# gs.net
KiCad netlist of a schematic drawn in EAGLE
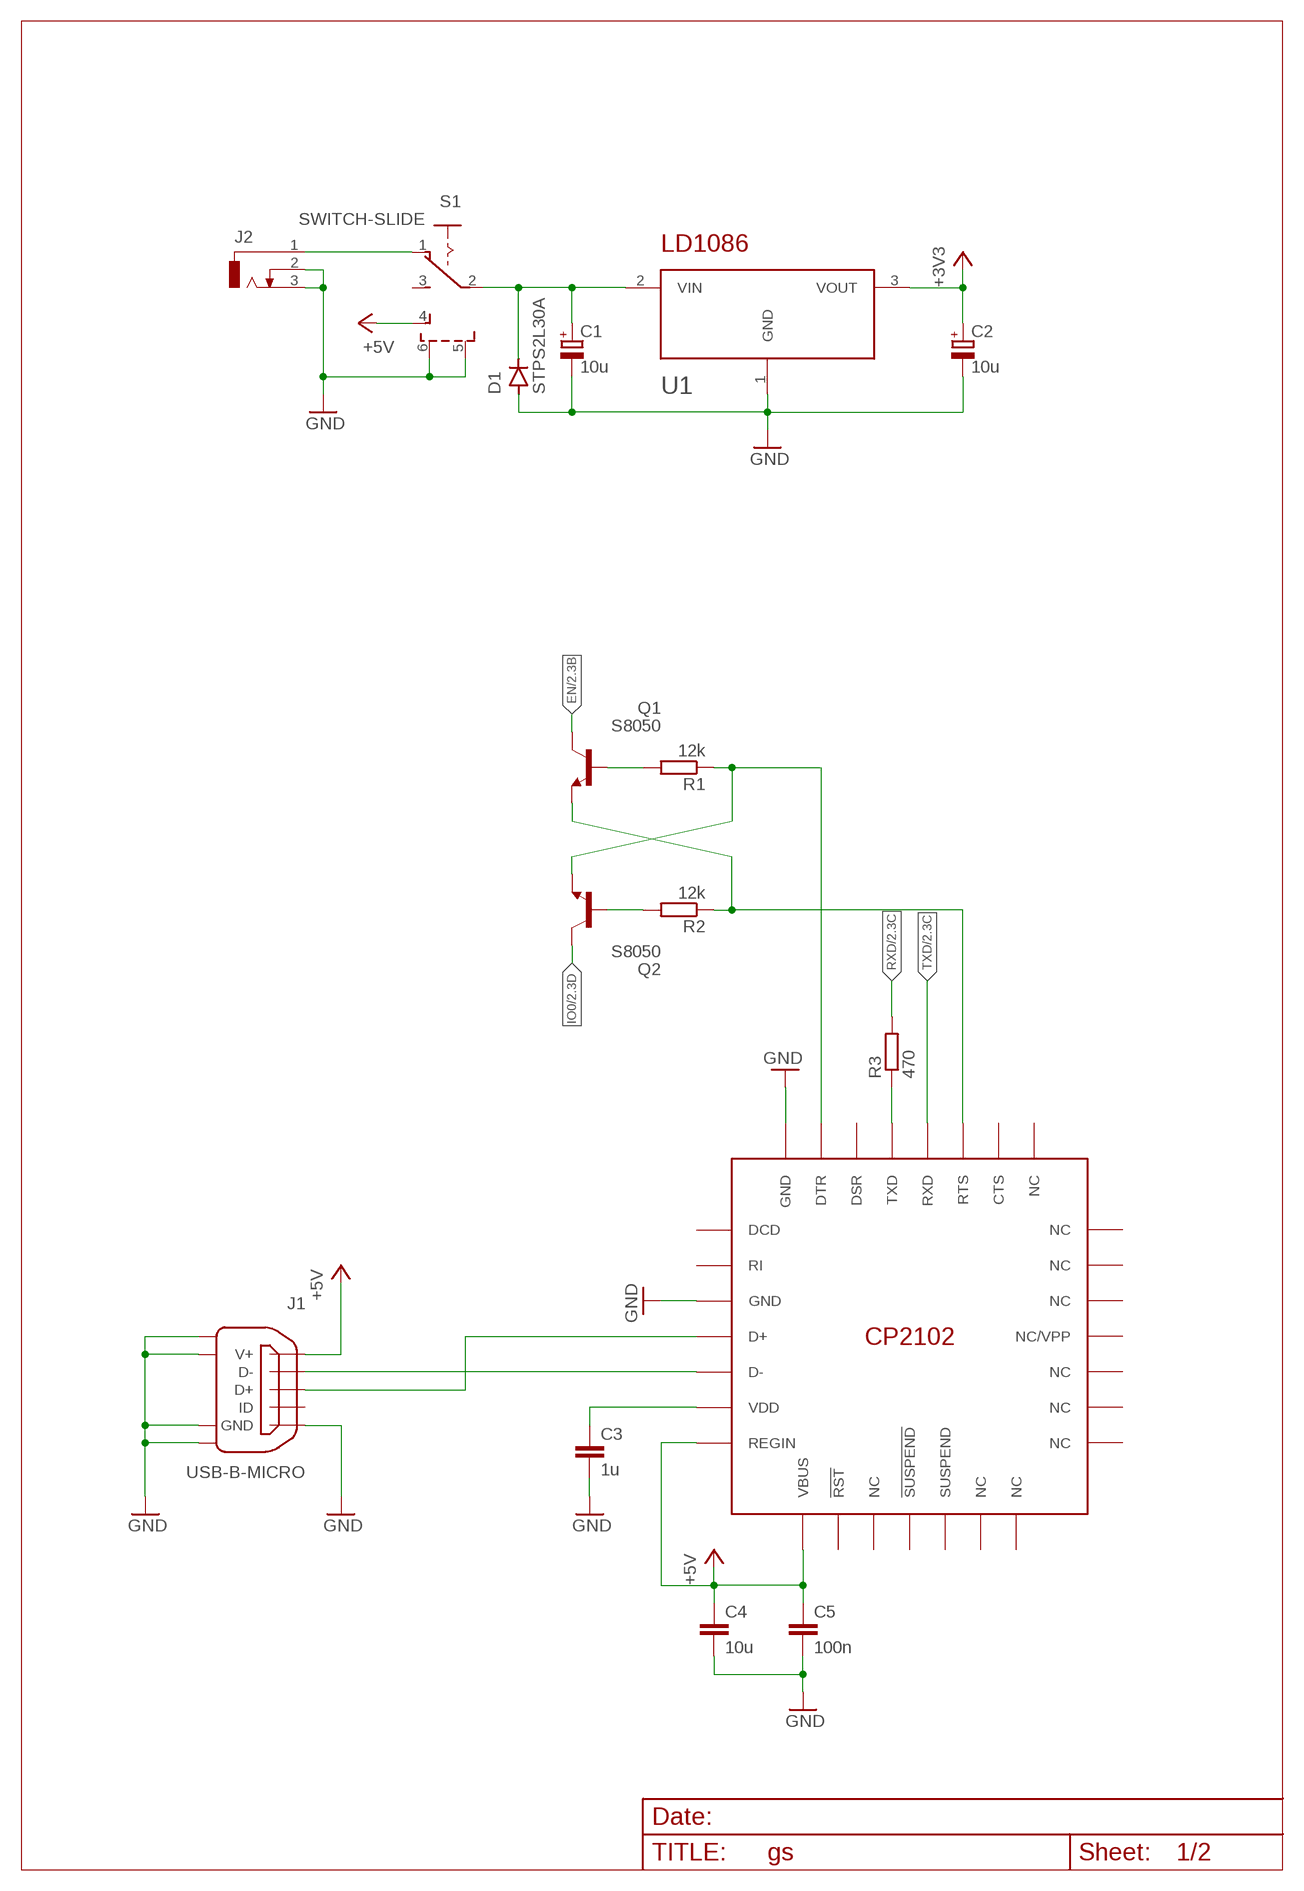
[diagram p0: schematic, sheet 1]
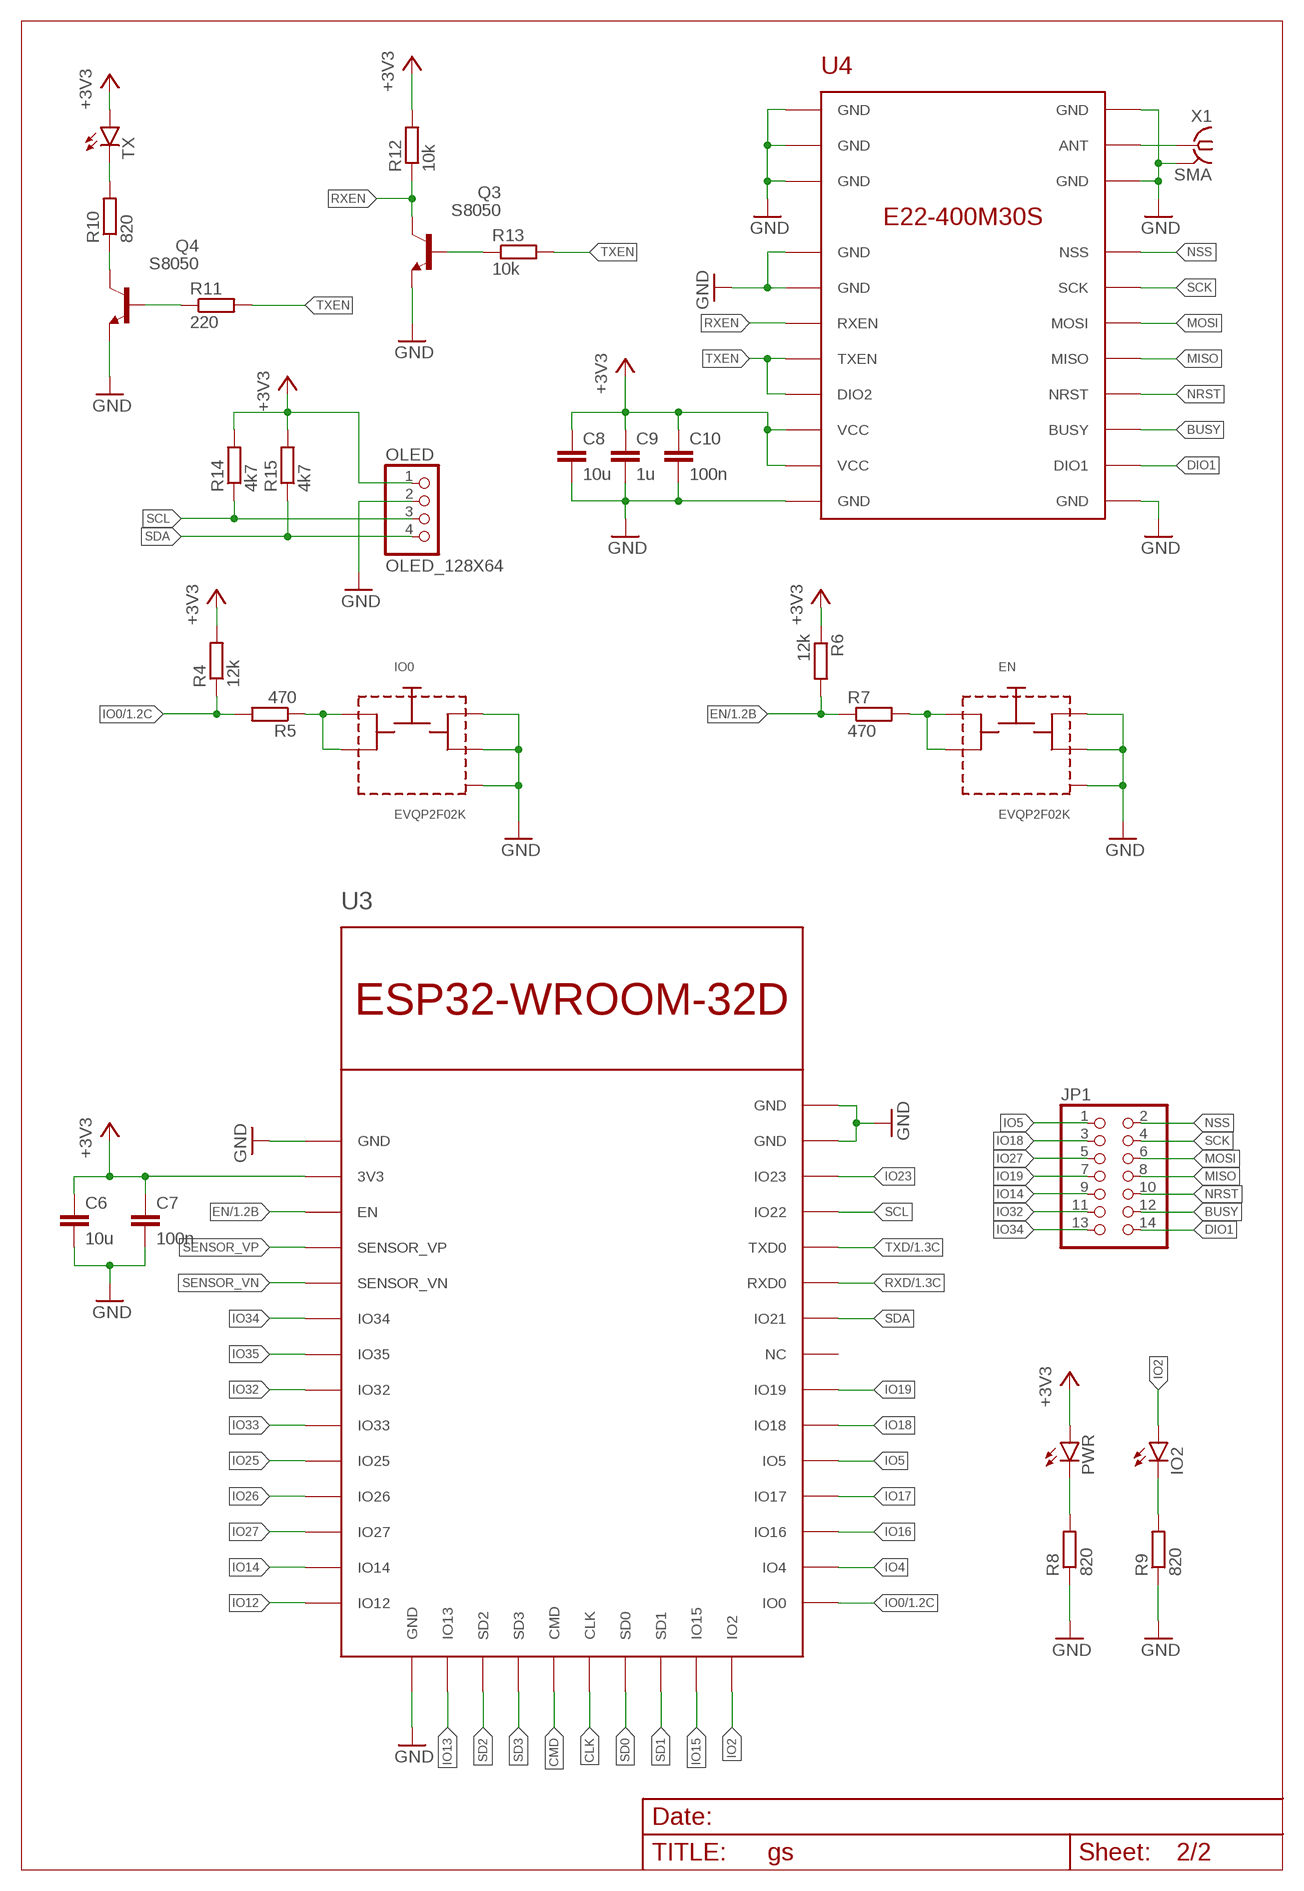
[diagram p1: schematic, sheet 2]

(export (version "E")
  (design (tool "Eeschema 10.0.6"))
  (components
    (comp (ref "C6")
      (value "10u")
      (footprint "eagle-import:C0805")
      (libsource (lib "eagle-import") (part "C-EUC0805"))
    )
    (comp (ref "C7")
      (value "100n")
      (footprint "eagle-import:C0805")
      (libsource (lib "eagle-import") (part "C-EUC0805"))
    )
    (comp (ref "C8")
      (value "10u")
      (footprint "eagle-import:C0805")
      (libsource (lib "eagle-import") (part "C-EUC0805"))
    )
    (comp (ref "C9")
      (value "1u")
      (footprint "eagle-import:C0805")
      (libsource (lib "eagle-import") (part "C-EUC0805"))
    )
    (comp (ref "C10")
      (value "100n")
      (footprint "eagle-import:C0805")
      (libsource (lib "eagle-import") (part "C-EUC0805"))
    )
    (comp (ref "EN")
      (value "EVQP2F02K")
      (footprint "eagle-import:EVQP2F02K")
      (libsource (lib "eagle-import") (part "EVQP2F02K"))
    )
    (comp (ref "IO0")
      (value "EVQP2F02K")
      (footprint "eagle-import:EVQP2F02K")
      (libsource (lib "eagle-import") (part "EVQP2F02K"))
    )
    (comp (ref "IO2")
      (value "LEDCHIP-LED0805")
      (footprint "eagle-import:CHIP-LED0805")
      (libsource (lib "eagle-import") (part "LEDCHIP-LED0805"))
    )
    (comp (ref "JP1")
      (value "PINHD-2X7")
      (footprint "eagle-import:2X07")
      (libsource (lib "eagle-import") (part "PINHD-2X7"))
    )
    (comp (ref "OLED")
      (value "OLED_128X64")
      (footprint "eagle-import:OLED_128X64")
      (libsource (lib "eagle-import") (part "OLED_128X64"))
    )
    (comp (ref "PWR")
      (value "LEDCHIP-LED0805")
      (footprint "eagle-import:CHIP-LED0805")
      (libsource (lib "eagle-import") (part "LEDCHIP-LED0805"))
    )
    (comp (ref "Q3")
      (value "S8050")
      (footprint "eagle-import:SOT95P237X110-3N")
      (libsource (lib "eagle-import") (part "S8050"))
    )
    (comp (ref "Q4")
      (value "S8050")
      (footprint "eagle-import:SOT95P237X110-3N")
      (libsource (lib "eagle-import") (part "S8050"))
    )
    (comp (ref "R4")
      (value "12k")
      (footprint "eagle-import:R0805")
      (libsource (lib "eagle-import") (part "R-EU_R0805"))
    )
    (comp (ref "R5")
      (value "470")
      (footprint "eagle-import:R0805")
      (libsource (lib "eagle-import") (part "R-EU_R0805"))
    )
    (comp (ref "R6")
      (value "12k")
      (footprint "eagle-import:R0805")
      (libsource (lib "eagle-import") (part "R-EU_R0805"))
    )
    (comp (ref "R7")
      (value "470")
      (footprint "eagle-import:R0805")
      (libsource (lib "eagle-import") (part "R-EU_R0805"))
    )
    (comp (ref "R8")
      (value "820")
      (footprint "eagle-import:R0805")
      (libsource (lib "eagle-import") (part "R-EU_R0805"))
    )
    (comp (ref "R9")
      (value "820")
      (footprint "eagle-import:R0805")
      (libsource (lib "eagle-import") (part "R-EU_R0805"))
    )
    (comp (ref "R10")
      (value "820")
      (footprint "eagle-import:R0805")
      (libsource (lib "eagle-import") (part "R-EU_R0805"))
    )
    (comp (ref "R11")
      (value "220")
      (footprint "eagle-import:R0805")
      (libsource (lib "eagle-import") (part "R-EU_R0805"))
    )
    (comp (ref "R12")
      (value "10k")
      (footprint "eagle-import:R0805")
      (libsource (lib "eagle-import") (part "R-EU_R0805"))
    )
    (comp (ref "R13")
      (value "10k")
      (footprint "eagle-import:R0805")
      (libsource (lib "eagle-import") (part "R-EU_R0805"))
    )
    (comp (ref "R14")
      (value "4k7")
      (footprint "eagle-import:R0805")
      (libsource (lib "eagle-import") (part "R-EU_R0805"))
    )
    (comp (ref "R15")
      (value "4k7")
      (footprint "eagle-import:R0805")
      (libsource (lib "eagle-import") (part "R-EU_R0805"))
    )
    (comp (ref "TX")
      (value "LEDCHIP-LED0805")
      (footprint "eagle-import:CHIP-LED0805")
      (libsource (lib "eagle-import") (part "LEDCHIP-LED0805"))
    )
    (comp (ref "U3")
      (value "ESP32-WROOM-32D")
      (footprint "eagle-import:ESP32-SOLO-1")
      (libsource (lib "eagle-import") (part "ESP32-WROOM-32D"))
    )
    (comp (ref "U4")
      (value "E22-400M30S")
      (footprint "eagle-import:E22-400M30S")
      (libsource (lib "eagle-import") (part "E22-400M30S"))
    )
    (comp (ref "X1")
      (value "SMA")
      (footprint "eagle-import:SMA")
      (fields (field (name "TME") "RF2145AT1750GHDW"))
      (libsource (lib "eagle-import") (part "SMA"))
    )
    (comp (ref "C1")
      (value "10u")
      (footprint "eagle-import:SMC_C")
      (libsource (lib "eagle-import") (part "CPOL-EUSMCC"))
    )
    (comp (ref "C2")
      (value "10u")
      (footprint "eagle-import:SMC_C")
      (libsource (lib "eagle-import") (part "CPOL-EUSMCC"))
    )
    (comp (ref "C3")
      (value "1u")
      (footprint "eagle-import:C0805")
      (libsource (lib "eagle-import") (part "C-EUC0805"))
    )
    (comp (ref "C4")
      (value "10u")
      (footprint "eagle-import:C0805")
      (libsource (lib "eagle-import") (part "C-EUC0805"))
    )
    (comp (ref "C5")
      (value "100n")
      (footprint "eagle-import:C0805")
      (libsource (lib "eagle-import") (part "C-EUC0805"))
    )
    (comp (ref "D1")
      (value "STPS2L30A")
      (footprint "eagle-import:DIOM4225X245N")
      (libsource (lib "eagle-import") (part "STPS2L30A"))
    )
    (comp (ref "J1")
      (value "USB-B-MICRO")
      (footprint "eagle-import:USB-B-MICRO")
      (libsource (lib "eagle-import") (part "USB-B-MICRO"))
    )
    (comp (ref "J2")
      (value "DCJ0303")
      (footprint "eagle-import:DCJ0303")
      (fields (field (name "TME") "1613-21"))
      (libsource (lib "eagle-import") (part "DCJ0303"))
    )
    (comp (ref "Q1")
      (value "S8050")
      (footprint "eagle-import:SOT95P237X110-3N")
      (libsource (lib "eagle-import") (part "S8050"))
    )
    (comp (ref "Q2")
      (value "S8050")
      (footprint "eagle-import:SOT95P237X110-3N")
      (libsource (lib "eagle-import") (part "S8050"))
    )
    (comp (ref "R1")
      (value "12k")
      (footprint "eagle-import:R0805")
      (libsource (lib "eagle-import") (part "R-EU_R0805"))
    )
    (comp (ref "R2")
      (value "12k")
      (footprint "eagle-import:R0805")
      (libsource (lib "eagle-import") (part "R-EU_R0805"))
    )
    (comp (ref "R3")
      (value "470")
      (footprint "eagle-import:R0805")
      (libsource (lib "eagle-import") (part "R-EU_R0805"))
    )
    (comp (ref "S1")
      (value "SWITCH-SLIDE")
      (footprint "eagle-import:SWITCH-SLIDE")
      (libsource (lib "eagle-import") (part "SWITCH-SLIDE"))
    )
    (comp (ref "U1")
      (value "LD1086DT33TR")
      (footprint "eagle-import:TO228P972X240-3N")
      (libsource (lib "eagle-import") (part "LD1086DT33TR"))
    )
    (comp (ref "U2")
      (value "CP2102")
      (footprint "eagle-import:QFN50P500X500X100-29T300N")
      (libsource (lib "eagle-import") (part "CP2102"))
    )
  )
  (nets
    (net (code "1") (name "+3V3") (class "Default")
      (node (ref "C10") (pin "1") (pinfunction "1_1") (pintype "passive"))
      (node (ref "C2") (pin "+") (pinfunction "+_+") (pintype "passive"))
      (node (ref "C6") (pin "1") (pinfunction "1_1") (pintype "passive"))
      (node (ref "C7") (pin "1") (pinfunction "1_1") (pintype "passive"))
      (node (ref "C8") (pin "1") (pinfunction "1_1") (pintype "passive"))
      (node (ref "C9") (pin "1") (pinfunction "1_1") (pintype "passive"))
      (node (ref "OLED") (pin "1") (pinfunction "1_1") (pintype "passive"))
      (node (ref "PWR") (pin "A") (pinfunction "A_A") (pintype "passive"))
      (node (ref "R12") (pin "2") (pinfunction "2_2") (pintype "passive"))
      (node (ref "R14") (pin "2") (pinfunction "2_2") (pintype "passive"))
      (node (ref "R15") (pin "2") (pinfunction "2_2") (pintype "passive"))
      (node (ref "R4") (pin "2") (pinfunction "2_2") (pintype "passive"))
      (node (ref "R6") (pin "1") (pinfunction "1_1") (pintype "passive"))
      (node (ref "TX") (pin "A") (pinfunction "A_A") (pintype "passive"))
      (node (ref "U1") (pin "3") (pinfunction "VOUT_3") (pintype "bidirectional"))
      (node (ref "U3") (pin "2") (pinfunction "3V3_2") (pintype "bidirectional"))
      (node (ref "U4") (pin "10") (pinfunction "VCC_10") (pintype "bidirectional"))
      (node (ref "U4") (pin "9") (pinfunction "VCC_9") (pintype "bidirectional"))
    )
    (net (code "2") (name "+5V") (class "Default")
      (node (ref "C4") (pin "1") (pinfunction "1_1") (pintype "passive"))
      (node (ref "C5") (pin "1") (pinfunction "1_1") (pintype "passive"))
      (node (ref "J1") (pin "1") (pinfunction "V+_1") (pintype "passive"))
      (node (ref "S1") (pin "4") (pinfunction "4_4") (pintype "passive"))
      (node (ref "U2") (pin "7") (pinfunction "REGIN_7") (pintype "bidirectional"))
      (node (ref "U2") (pin "8") (pinfunction "VBUS_8") (pintype "bidirectional"))
    )
    (net (code "3") (name "BUSY") (class "Default")
      (node (ref "JP1") (pin "12") (pinfunction "12_12") (pintype "passive"))
      (node (ref "U4") (pin "14") (pinfunction "BUSY_14") (pintype "bidirectional"))
    )
    (net (code "4") (name "CLK") (class "Default")
      (node (ref "U3") (pin "20") (pinfunction "CLK_20") (pintype "bidirectional"))
    )
    (net (code "5") (name "CMD") (class "Default")
      (node (ref "U3") (pin "19") (pinfunction "CMD_19") (pintype "bidirectional"))
    )
    (net (code "6") (name "DIO1") (class "Default")
      (node (ref "JP1") (pin "14") (pinfunction "14_14") (pintype "passive"))
      (node (ref "U4") (pin "13") (pinfunction "DIO1_13") (pintype "bidirectional"))
    )
    (net (code "7") (name "EN") (class "Default")
      (node (ref "Q1") (pin "3") (pinfunction "C_3") (pintype "passive"))
      (node (ref "R6") (pin "2") (pinfunction "2_2") (pintype "passive"))
      (node (ref "R7") (pin "1") (pinfunction "1_1") (pintype "passive"))
      (node (ref "U3") (pin "3") (pinfunction "EN_3") (pintype "bidirectional"))
    )
    (net (code "8") (name "GND") (class "Default")
      (node (ref "C1") (pin "-") (pinfunction "-_-") (pintype "passive"))
      (node (ref "C10") (pin "2") (pinfunction "2_2") (pintype "passive"))
      (node (ref "C2") (pin "-") (pinfunction "-_-") (pintype "passive"))
      (node (ref "C3") (pin "2") (pinfunction "2_2") (pintype "passive"))
      (node (ref "C4") (pin "2") (pinfunction "2_2") (pintype "passive"))
      (node (ref "C5") (pin "2") (pinfunction "2_2") (pintype "passive"))
      (node (ref "C6") (pin "2") (pinfunction "2_2") (pintype "passive"))
      (node (ref "C7") (pin "2") (pinfunction "2_2") (pintype "passive"))
      (node (ref "C8") (pin "2") (pinfunction "2_2") (pintype "passive"))
      (node (ref "C9") (pin "2") (pinfunction "2_2") (pintype "passive"))
      (node (ref "D1") (pin "2") (pinfunction "A_2") (pintype "passive"))
      (node (ref "EN") (pin "3") (pinfunction "P$3_3") (pintype "passive"))
      (node (ref "EN") (pin "4") (pinfunction "P$4_4") (pintype "passive"))
      (node (ref "EN") (pin "5") (pinfunction "P$5_5") (pintype "passive"))
      (node (ref "IO0") (pin "3") (pinfunction "P$3_3") (pintype "passive"))
      (node (ref "IO0") (pin "4") (pinfunction "P$4_4") (pintype "passive"))
      (node (ref "IO0") (pin "5") (pinfunction "P$5_5") (pintype "passive"))
      (node (ref "J1") (pin "5") (pinfunction "GND_5") (pintype "passive"))
      (node (ref "J1") (pin "6") (pinfunction "6_6") (pintype "passive"))
      (node (ref "J1") (pin "7") (pinfunction "7_7") (pintype "passive"))
      (node (ref "J1") (pin "8") (pinfunction "8_8") (pintype "passive"))
      (node (ref "J1") (pin "9") (pinfunction "9_9") (pintype "passive"))
      (node (ref "J2") (pin "2") (pinfunction "2_2") (pintype "passive"))
      (node (ref "J2") (pin "3") (pinfunction "3_3") (pintype "passive"))
      (node (ref "OLED") (pin "2") (pinfunction "2_2") (pintype "passive"))
      (node (ref "Q3") (pin "2") (pinfunction "E_2") (pintype "passive"))
      (node (ref "Q4") (pin "2") (pinfunction "E_2") (pintype "passive"))
      (node (ref "R8") (pin "1") (pinfunction "1_1") (pintype "passive"))
      (node (ref "R9") (pin "1") (pinfunction "1_1") (pintype "passive"))
      (node (ref "S1") (pin "5") (pinfunction "S1_5") (pintype "passive"))
      (node (ref "S1") (pin "6") (pinfunction "S2_6") (pintype "passive"))
      (node (ref "U1") (pin "1") (pinfunction "GND_1") (pintype "bidirectional"))
      (node (ref "U2") (pin "29") (pinfunction "GND_29") (pintype "bidirectional"))
      (node (ref "U2") (pin "3") (pinfunction "GND_3") (pintype "bidirectional"))
      (node (ref "U3") (pin "1") (pinfunction "GND_1") (pintype "bidirectional"))
      (node (ref "U3") (pin "15") (pinfunction "GND_15") (pintype "bidirectional"))
      (node (ref "U3") (pin "38") (pinfunction "GND_38") (pintype "bidirectional"))
      (node (ref "U3") (pin "39") (pinfunction "GND_39") (pintype "bidirectional"))
      (node (ref "U4") (pin "1") (pinfunction "GND_1") (pintype "bidirectional"))
      (node (ref "U4") (pin "11") (pinfunction "GND_11") (pintype "bidirectional"))
      (node (ref "U4") (pin "12") (pinfunction "GND_12") (pintype "bidirectional"))
      (node (ref "U4") (pin "2") (pinfunction "GND_2") (pintype "bidirectional"))
      (node (ref "U4") (pin "20") (pinfunction "GND_20") (pintype "bidirectional"))
      (node (ref "U4") (pin "22") (pinfunction "GND_22") (pintype "bidirectional"))
      (node (ref "U4") (pin "3") (pinfunction "GND_3") (pintype "bidirectional"))
      (node (ref "U4") (pin "4") (pinfunction "GND_4") (pintype "bidirectional"))
      (node (ref "U4") (pin "5") (pinfunction "GND_5") (pintype "bidirectional"))
      (node (ref "X1") (pin "G@1") (pinfunction "2_G@1") (pintype "passive"))
      (node (ref "X1") (pin "G@2") (pinfunction "2_G@2") (pintype "passive"))
      (node (ref "X1") (pin "G@3") (pinfunction "2_G@3") (pintype "passive"))
      (node (ref "X1") (pin "G@4") (pinfunction "2_G@4") (pintype "passive"))
    )
    (net (code "9") (name "IO0") (class "Default")
      (node (ref "Q2") (pin "3") (pinfunction "C_3") (pintype "passive"))
      (node (ref "R4") (pin "1") (pinfunction "1_1") (pintype "passive"))
      (node (ref "R5") (pin "2") (pinfunction "2_2") (pintype "passive"))
      (node (ref "U3") (pin "25") (pinfunction "IO0_25") (pintype "bidirectional"))
    )
    (net (code "10") (name "IO2") (class "Default")
      (node (ref "IO2") (pin "A") (pinfunction "A_A") (pintype "passive"))
      (node (ref "U3") (pin "24") (pinfunction "IO2_24") (pintype "bidirectional"))
    )
    (net (code "11") (name "IO4") (class "Default")
      (node (ref "U3") (pin "26") (pinfunction "IO4_26") (pintype "bidirectional"))
    )
    (net (code "12") (name "IO5") (class "Default")
      (node (ref "JP1") (pin "1") (pinfunction "1_1") (pintype "passive"))
      (node (ref "U3") (pin "29") (pinfunction "IO5_29") (pintype "bidirectional"))
    )
    (net (code "13") (name "IO12") (class "Default")
      (node (ref "U3") (pin "14") (pinfunction "IO12_14") (pintype "bidirectional"))
    )
    (net (code "14") (name "IO13") (class "Default")
      (node (ref "U3") (pin "16") (pinfunction "IO13_16") (pintype "bidirectional"))
    )
    (net (code "15") (name "IO14") (class "Default")
      (node (ref "JP1") (pin "9") (pinfunction "9_9") (pintype "passive"))
      (node (ref "U3") (pin "13") (pinfunction "IO14_13") (pintype "bidirectional"))
    )
    (net (code "16") (name "IO15") (class "Default")
      (node (ref "U3") (pin "23") (pinfunction "IO15_23") (pintype "bidirectional"))
    )
    (net (code "17") (name "IO16") (class "Default")
      (node (ref "U3") (pin "27") (pinfunction "IO16_27") (pintype "bidirectional"))
    )
    (net (code "18") (name "IO17") (class "Default")
      (node (ref "U3") (pin "28") (pinfunction "IO17_28") (pintype "bidirectional"))
    )
    (net (code "19") (name "IO18") (class "Default")
      (node (ref "JP1") (pin "3") (pinfunction "3_3") (pintype "passive"))
      (node (ref "U3") (pin "30") (pinfunction "IO18_30") (pintype "bidirectional"))
    )
    (net (code "20") (name "IO19") (class "Default")
      (node (ref "JP1") (pin "7") (pinfunction "7_7") (pintype "passive"))
      (node (ref "U3") (pin "31") (pinfunction "IO19_31") (pintype "bidirectional"))
    )
    (net (code "21") (name "IO23") (class "Default")
      (node (ref "U3") (pin "37") (pinfunction "IO23_37") (pintype "bidirectional"))
    )
    (net (code "22") (name "IO25") (class "Default")
      (node (ref "U3") (pin "10") (pinfunction "IO25_10") (pintype "bidirectional"))
    )
    (net (code "23") (name "IO26") (class "Default")
      (node (ref "U3") (pin "11") (pinfunction "IO26_11") (pintype "bidirectional"))
    )
    (net (code "24") (name "IO27") (class "Default")
      (node (ref "JP1") (pin "5") (pinfunction "5_5") (pintype "passive"))
      (node (ref "U3") (pin "12") (pinfunction "IO27_12") (pintype "bidirectional"))
    )
    (net (code "25") (name "IO32") (class "Default")
      (node (ref "JP1") (pin "11") (pinfunction "11_11") (pintype "passive"))
      (node (ref "U3") (pin "8") (pinfunction "IO32_8") (pintype "bidirectional"))
    )
    (net (code "26") (name "IO33") (class "Default")
      (node (ref "U3") (pin "9") (pinfunction "IO33_9") (pintype "bidirectional"))
    )
    (net (code "27") (name "IO34") (class "Default")
      (node (ref "JP1") (pin "13") (pinfunction "13_13") (pintype "passive"))
      (node (ref "U3") (pin "6") (pinfunction "IO34_6") (pintype "bidirectional"))
    )
    (net (code "28") (name "IO35") (class "Default")
      (node (ref "U3") (pin "7") (pinfunction "IO35_7") (pintype "bidirectional"))
    )
    (net (code "29") (name "MISO") (class "Default")
      (node (ref "JP1") (pin "8") (pinfunction "8_8") (pintype "passive"))
      (node (ref "U4") (pin "16") (pinfunction "MISO_16") (pintype "bidirectional"))
    )
    (net (code "30") (name "MOSI") (class "Default")
      (node (ref "JP1") (pin "6") (pinfunction "6_6") (pintype "passive"))
      (node (ref "U4") (pin "17") (pinfunction "MOSI_17") (pintype "bidirectional"))
    )
    (net (code "31") (name "NRST") (class "Default")
      (node (ref "JP1") (pin "10") (pinfunction "10_10") (pintype "passive"))
      (node (ref "U4") (pin "15") (pinfunction "NRST_15") (pintype "bidirectional"))
    )
    (net (code "32") (name "NSS") (class "Default")
      (node (ref "JP1") (pin "2") (pinfunction "2_2") (pintype "passive"))
      (node (ref "U4") (pin "19") (pinfunction "NSS_19") (pintype "bidirectional"))
    )
    (net (code "33") (name "Net-(D1-C)") (class "Default")
      (node (ref "C1") (pin "+") (pinfunction "+_+") (pintype "passive"))
      (node (ref "D1") (pin "1") (pinfunction "C_1") (pintype "passive"))
      (node (ref "S1") (pin "2") (pinfunction "2_2") (pintype "passive"))
      (node (ref "U1") (pin "2") (pinfunction "VIN_2") (pintype "bidirectional"))
    )
    (net (code "34") (name "Net-(EN-P$1)") (class "Default")
      (node (ref "EN") (pin "1") (pinfunction "P$1_1") (pintype "passive"))
      (node (ref "EN") (pin "2") (pinfunction "P$2_2") (pintype "passive"))
      (node (ref "R7") (pin "2") (pinfunction "2_2") (pintype "passive"))
    )
    (net (code "35") (name "Net-(IO0-P$1)") (class "Default")
      (node (ref "IO0") (pin "1") (pinfunction "P$1_1") (pintype "passive"))
      (node (ref "IO0") (pin "2") (pinfunction "P$2_2") (pintype "passive"))
      (node (ref "R5") (pin "1") (pinfunction "1_1") (pintype "passive"))
    )
    (net (code "36") (name "Net-(IO2-PadC)") (class "Default")
      (node (ref "IO2") (pin "C") (pinfunction "C_C") (pintype "passive"))
      (node (ref "R9") (pin "2") (pinfunction "2_2") (pintype "passive"))
    )
    (net (code "37") (name "Net-(J1-D+)") (class "Default")
      (node (ref "J1") (pin "3") (pinfunction "D+_3") (pintype "passive"))
      (node (ref "U2") (pin "4") (pinfunction "D+_4") (pintype "bidirectional"))
    )
    (net (code "38") (name "Net-(J1-D-)") (class "Default")
      (node (ref "J1") (pin "2") (pinfunction "D-_2") (pintype "passive"))
      (node (ref "U2") (pin "5") (pinfunction "D-_5") (pintype "bidirectional"))
    )
    (net (code "39") (name "Net-(J2-Pad1)") (class "Default")
      (node (ref "J2") (pin "1") (pinfunction "1_1") (pintype "passive"))
      (node (ref "S1") (pin "1") (pinfunction "1_1") (pintype "passive"))
    )
    (net (code "40") (name "Net-(PWR-PadC)") (class "Default")
      (node (ref "PWR") (pin "C") (pinfunction "C_C") (pintype "passive"))
      (node (ref "R8") (pin "2") (pinfunction "2_2") (pintype "passive"))
    )
    (net (code "41") (name "Net-(Q1-B)") (class "Default")
      (node (ref "Q1") (pin "1") (pinfunction "B_1") (pintype "passive"))
      (node (ref "R1") (pin "2") (pinfunction "2_2") (pintype "passive"))
    )
    (net (code "42") (name "Net-(Q1-E)") (class "Default")
      (node (ref "Q1") (pin "2") (pinfunction "E_2") (pintype "passive"))
      (node (ref "R2") (pin "1") (pinfunction "1_1") (pintype "passive"))
      (node (ref "U2") (pin "24") (pinfunction "RTS_24") (pintype "bidirectional"))
    )
    (net (code "43") (name "Net-(Q2-B)") (class "Default")
      (node (ref "Q2") (pin "1") (pinfunction "B_1") (pintype "passive"))
      (node (ref "R2") (pin "2") (pinfunction "2_2") (pintype "passive"))
    )
    (net (code "44") (name "Net-(Q2-E)") (class "Default")
      (node (ref "Q2") (pin "2") (pinfunction "E_2") (pintype "passive"))
      (node (ref "R1") (pin "1") (pinfunction "1_1") (pintype "passive"))
      (node (ref "U2") (pin "28") (pinfunction "DTR_28") (pintype "bidirectional"))
    )
    (net (code "45") (name "Net-(Q3-B)") (class "Default")
      (node (ref "Q3") (pin "1") (pinfunction "B_1") (pintype "passive"))
      (node (ref "R13") (pin "1") (pinfunction "1_1") (pintype "passive"))
    )
    (net (code "46") (name "Net-(Q4-B)") (class "Default")
      (node (ref "Q4") (pin "1") (pinfunction "B_1") (pintype "passive"))
      (node (ref "R11") (pin "1") (pinfunction "1_1") (pintype "passive"))
    )
    (net (code "47") (name "Net-(Q4-C)") (class "Default")
      (node (ref "Q4") (pin "3") (pinfunction "C_3") (pintype "passive"))
      (node (ref "R10") (pin "1") (pinfunction "1_1") (pintype "passive"))
    )
    (net (code "48") (name "Net-(R10-Pad2)") (class "Default")
      (node (ref "R10") (pin "2") (pinfunction "2_2") (pintype "passive"))
      (node (ref "TX") (pin "C") (pinfunction "C_C") (pintype "passive"))
    )
    (net (code "49") (name "Net-(U2-TXD)") (class "Default")
      (node (ref "R3") (pin "1") (pinfunction "1_1") (pintype "passive"))
      (node (ref "U2") (pin "26") (pinfunction "TXD_26") (pintype "bidirectional"))
    )
    (net (code "50") (name "Net-(U2-VDD)") (class "Default")
      (node (ref "C3") (pin "1") (pinfunction "1_1") (pintype "passive"))
      (node (ref "U2") (pin "6") (pinfunction "VDD_6") (pintype "bidirectional"))
    )
    (net (code "51") (name "Net-(U4-ANT)") (class "Default")
      (node (ref "U4") (pin "21") (pinfunction "ANT_21") (pintype "bidirectional"))
      (node (ref "X1") (pin "1") (pinfunction "1_1") (pintype "passive"))
    )
    (net (code "52") (name "RXD") (class "Default")
      (node (ref "R3") (pin "2") (pinfunction "2_2") (pintype "passive"))
      (node (ref "U3") (pin "34") (pinfunction "RXD0_34") (pintype "bidirectional"))
    )
    (net (code "53") (name "RXEN") (class "Default")
      (node (ref "Q3") (pin "3") (pinfunction "C_3") (pintype "passive"))
      (node (ref "R12") (pin "1") (pinfunction "1_1") (pintype "passive"))
      (node (ref "U4") (pin "6") (pinfunction "RXEN_6") (pintype "bidirectional"))
    )
    (net (code "54") (name "SCK") (class "Default")
      (node (ref "JP1") (pin "4") (pinfunction "4_4") (pintype "passive"))
      (node (ref "U4") (pin "18") (pinfunction "SCK_18") (pintype "bidirectional"))
    )
    (net (code "55") (name "SCL") (class "Default")
      (node (ref "OLED") (pin "3") (pinfunction "3_3") (pintype "passive"))
      (node (ref "R14") (pin "1") (pinfunction "1_1") (pintype "passive"))
      (node (ref "U3") (pin "36") (pinfunction "IO22_36") (pintype "bidirectional"))
    )
    (net (code "56") (name "SD0") (class "Default")
      (node (ref "U3") (pin "21") (pinfunction "SD0_21") (pintype "bidirectional"))
    )
    (net (code "57") (name "SD1") (class "Default")
      (node (ref "U3") (pin "22") (pinfunction "SD1_22") (pintype "bidirectional"))
    )
    (net (code "58") (name "SD2") (class "Default")
      (node (ref "U3") (pin "17") (pinfunction "SD2_17") (pintype "bidirectional"))
    )
    (net (code "59") (name "SD3") (class "Default")
      (node (ref "U3") (pin "18") (pinfunction "SD3_18") (pintype "bidirectional"))
    )
    (net (code "60") (name "SDA") (class "Default")
      (node (ref "OLED") (pin "4") (pinfunction "4_4") (pintype "passive"))
      (node (ref "R15") (pin "1") (pinfunction "1_1") (pintype "passive"))
      (node (ref "U3") (pin "33") (pinfunction "IO21_33") (pintype "bidirectional"))
    )
    (net (code "61") (name "SENSOR_VN") (class "Default")
      (node (ref "U3") (pin "5") (pinfunction "SENSOR_VN_5") (pintype "bidirectional"))
    )
    (net (code "62") (name "SENSOR_VP") (class "Default")
      (node (ref "U3") (pin "4") (pinfunction "SENSOR_VP_4") (pintype "bidirectional"))
    )
    (net (code "63") (name "TXD") (class "Default")
      (node (ref "U2") (pin "25") (pinfunction "RXD_25") (pintype "bidirectional"))
      (node (ref "U3") (pin "35") (pinfunction "TXD0_35") (pintype "bidirectional"))
    )
    (net (code "64") (name "TXEN") (class "Default")
      (node (ref "R11") (pin "2") (pinfunction "2_2") (pintype "passive"))
      (node (ref "R13") (pin "2") (pinfunction "2_2") (pintype "passive"))
      (node (ref "U4") (pin "7") (pinfunction "TXEN_7") (pintype "bidirectional"))
      (node (ref "U4") (pin "8") (pinfunction "DIO2_8") (pintype "bidirectional"))
    )
    (net (code "65") (name "unconnected-(J1-ID-Pad4)") (class "Default")
      (node (ref "J1") (pin "4") (pinfunction "ID_4") (pintype "passive"))
    )
    (net (code "66") (name "unconnected-(S1-Pad3)") (class "Default")
      (node (ref "S1") (pin "3") (pinfunction "3_3") (pintype "passive"))
    )
    (net (code "67") (name "unconnected-(U2-CTS-Pad23)") (class "Default")
      (node (ref "U2") (pin "23") (pinfunction "CTS_23") (pintype "bidirectional"))
    )
    (net (code "68") (name "unconnected-(U2-DCD-Pad1)") (class "Default")
      (node (ref "U2") (pin "1") (pinfunction "DCD_1") (pintype "bidirectional"))
    )
    (net (code "69") (name "unconnected-(U2-DSR-Pad27)") (class "Default")
      (node (ref "U2") (pin "27") (pinfunction "DSR_27") (pintype "bidirectional"))
    )
    (net (code "70") (name "unconnected-(U2-NC-Pad10)") (class "Default")
      (node (ref "U2") (pin "10") (pinfunction "NC_10") (pintype "bidirectional"))
    )
    (net (code "71") (name "unconnected-(U2-NC-Pad13)") (class "Default")
      (node (ref "U2") (pin "13") (pinfunction "NC_13") (pintype "bidirectional"))
    )
    (net (code "72") (name "unconnected-(U2-NC-Pad14)") (class "Default")
      (node (ref "U2") (pin "14") (pinfunction "NC_14") (pintype "bidirectional"))
    )
    (net (code "73") (name "unconnected-(U2-NC-Pad15)") (class "Default")
      (node (ref "U2") (pin "15") (pinfunction "NC_15") (pintype "bidirectional"))
    )
    (net (code "74") (name "unconnected-(U2-NC-Pad16)") (class "Default")
      (node (ref "U2") (pin "16") (pinfunction "NC_16") (pintype "bidirectional"))
    )
    (net (code "75") (name "unconnected-(U2-NC-Pad17)") (class "Default")
      (node (ref "U2") (pin "17") (pinfunction "NC_17") (pintype "bidirectional"))
    )
    (net (code "76") (name "unconnected-(U2-NC-Pad19)") (class "Default")
      (node (ref "U2") (pin "19") (pinfunction "NC_19") (pintype "bidirectional"))
    )
    (net (code "77") (name "unconnected-(U2-NC-Pad20)") (class "Default")
      (node (ref "U2") (pin "20") (pinfunction "NC_20") (pintype "bidirectional"))
    )
    (net (code "78") (name "unconnected-(U2-NC-Pad21)") (class "Default")
      (node (ref "U2") (pin "21") (pinfunction "NC_21") (pintype "bidirectional"))
    )
    (net (code "79") (name "unconnected-(U2-NC-Pad22)") (class "Default")
      (node (ref "U2") (pin "22") (pinfunction "NC_22") (pintype "bidirectional"))
    )
    (net (code "80") (name "unconnected-(U2-NC{slash}VPP-Pad18)") (class "Default")
      (node (ref "U2") (pin "18") (pinfunction "NC/VPP_18") (pintype "bidirectional"))
    )
    (net (code "81") (name "unconnected-(U2-RI-Pad2)") (class "Default")
      (node (ref "U2") (pin "2") (pinfunction "RI_2") (pintype "bidirectional"))
    )
    (net (code "82") (name "unconnected-(U2-SUSPEND-Pad12)") (class "Default")
      (node (ref "U2") (pin "12") (pinfunction "SUSPEND_12") (pintype "bidirectional"))
    )
    (net (code "83") (name "unconnected-(U2-~{RST}-Pad9)") (class "Default")
      (node (ref "U2") (pin "9") (pinfunction "~{RST}_9") (pintype "bidirectional"))
    )
    (net (code "84") (name "unconnected-(U2-~{SUSPEND}-Pad11)") (class "Default")
      (node (ref "U2") (pin "11") (pinfunction "~{SUSPEND}_11") (pintype "bidirectional"))
    )
    (net (code "85") (name "unconnected-(U3-NC-Pad32)") (class "Default")
      (node (ref "U3") (pin "32") (pinfunction "NC_32") (pintype "bidirectional"))
    )
  )
)
